# LeftInterface.net
KiCad netlist of a schematic drawn in Altium Designer
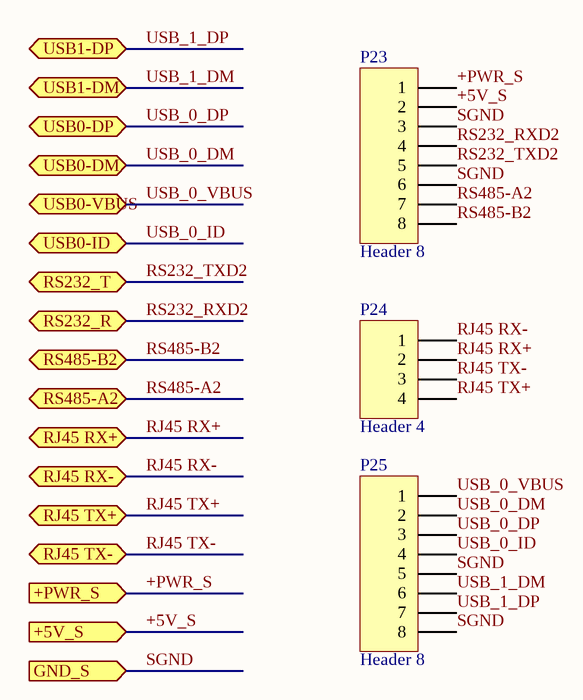
[diagram p0: LeftInterface.SchDoc]

(export (version "E")
  (design (tool "Eeschema 10.0.6"))
  (components
    (comp (ref "P23")
      (value "Header 8")
      (footprint "DS1X8-2.54")
      (description "Header, 8-Pin")
      (fields (field (name "PUBLISHER") "Altium Limited"))
      (libsource (lib "Miscellaneous Connectors") (part "Header 8"))
    )
    (comp (ref "P24")
      (value "Header 4")
      (footprint "DS1X4-2.54")
      (description "Header, 4-Pin")
      (fields (field (name "PUBLISHER") "Altium Limited"))
      (libsource (lib "Miscellaneous Connectors") (part "Header 4"))
    )
    (comp (ref "P25")
      (value "Header 8")
      (footprint "DS1X8-2.54")
      (description "Header, 8-Pin")
      (fields (field (name "PUBLISHER") "Altium Limited"))
      (libsource (lib "Miscellaneous Connectors") (part "Header 8"))
    )
  )
  (nets
    (net (code "1") (name "/+5V_S") (class "Default")
      (node (ref "P23") (pin "2") (pinfunction "2_2") (pintype "passive"))
    )
    (net (code "2") (name "/+PWR_S") (class "Default")
      (node (ref "P23") (pin "1") (pinfunction "1_1") (pintype "passive"))
    )
    (net (code "3") (name "/RJ45 RX+") (class "Default")
      (node (ref "P24") (pin "2") (pinfunction "2_2") (pintype "passive"))
    )
    (net (code "4") (name "/RJ45 RX-") (class "Default")
      (node (ref "P24") (pin "1") (pinfunction "1_1") (pintype "passive"))
    )
    (net (code "5") (name "/RJ45 TX+") (class "Default")
      (node (ref "P24") (pin "4") (pinfunction "4_4") (pintype "passive"))
    )
    (net (code "6") (name "/RJ45 TX-") (class "Default")
      (node (ref "P24") (pin "3") (pinfunction "3_3") (pintype "passive"))
    )
    (net (code "7") (name "/RS232_RXD2") (class "Default")
      (node (ref "P23") (pin "4") (pinfunction "4_4") (pintype "passive"))
    )
    (net (code "8") (name "/RS232_TXD2") (class "Default")
      (node (ref "P23") (pin "5") (pinfunction "5_5") (pintype "passive"))
    )
    (net (code "9") (name "/RS485-A2") (class "Default")
      (node (ref "P23") (pin "7") (pinfunction "7_7") (pintype "passive"))
    )
    (net (code "10") (name "/RS485-B2") (class "Default")
      (node (ref "P23") (pin "8") (pinfunction "8_8") (pintype "passive"))
    )
    (net (code "11") (name "/SGND") (class "Default")
      (node (ref "P23") (pin "3") (pinfunction "3_3") (pintype "passive"))
      (node (ref "P23") (pin "6") (pinfunction "6_6") (pintype "passive"))
      (node (ref "P25") (pin "5") (pinfunction "5_5") (pintype "passive"))
      (node (ref "P25") (pin "8") (pinfunction "8_8") (pintype "passive"))
    )
    (net (code "12") (name "/USB_0_DM") (class "Default")
      (node (ref "P25") (pin "2") (pinfunction "2_2") (pintype "passive"))
    )
    (net (code "13") (name "/USB_0_DP") (class "Default")
      (node (ref "P25") (pin "3") (pinfunction "3_3") (pintype "passive"))
    )
    (net (code "14") (name "/USB_0_ID") (class "Default")
      (node (ref "P25") (pin "4") (pinfunction "4_4") (pintype "passive"))
    )
    (net (code "15") (name "/USB_0_VBUS") (class "Default")
      (node (ref "P25") (pin "1") (pinfunction "1_1") (pintype "passive"))
    )
    (net (code "16") (name "/USB_1_DM") (class "Default")
      (node (ref "P25") (pin "6") (pinfunction "6_6") (pintype "passive"))
    )
    (net (code "17") (name "/USB_1_DP") (class "Default")
      (node (ref "P25") (pin "7") (pinfunction "7_7") (pintype "passive"))
    )
  )
)
